# shiftregboard.net
KiCad netlist of a schematic drawn in EAGLE
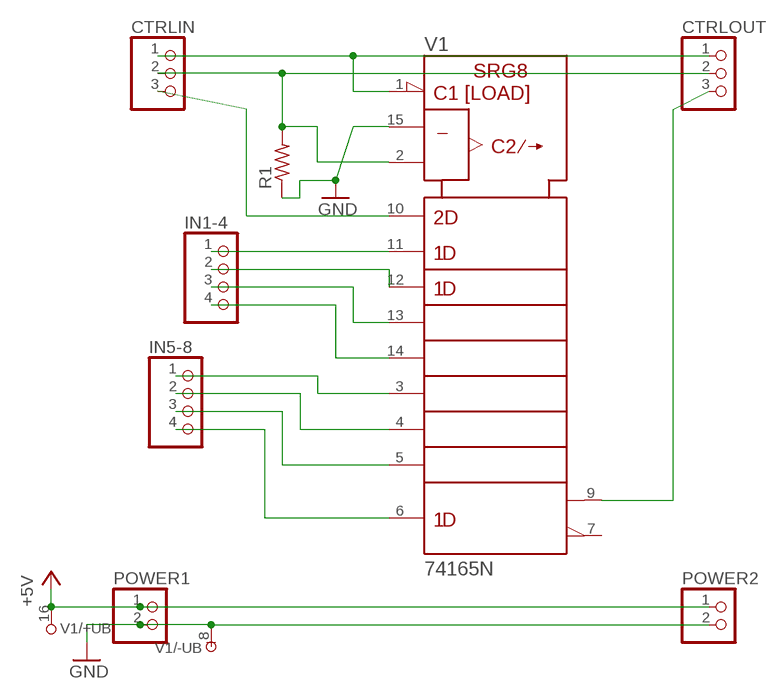
[diagram p0: schematic, sheet 1]

(export (version "E")
  (design (tool "Eeschema 10.0.6"))
  (components
    (comp (ref "CTRLIN")
      (value "PINHD-1X3")
      (footprint "eagle-import:1X03")
      (libsource (lib "eagle-import") (part "PINHD-1X3"))
    )
    (comp (ref "CTRLOUT")
      (value "PINHD-1X3")
      (footprint "eagle-import:1X03")
      (libsource (lib "eagle-import") (part "PINHD-1X3"))
    )
    (comp (ref "IN1-4")
      (value "PINHD-1X4")
      (footprint "eagle-import:1X04")
      (libsource (lib "eagle-import") (part "PINHD-1X4"))
    )
    (comp (ref "IN5-8")
      (value "PINHD-1X4")
      (footprint "eagle-import:1X04")
      (libsource (lib "eagle-import") (part "PINHD-1X4"))
    )
    (comp (ref "POWER1")
      (value "PINHD-1X2")
      (footprint "eagle-import:1X02")
      (libsource (lib "eagle-import") (part "PINHD-1X2"))
    )
    (comp (ref "POWER2")
      (value "PINHD-1X2")
      (footprint "eagle-import:1X02")
      (libsource (lib "eagle-import") (part "PINHD-1X2"))
    )
    (comp (ref "R1")
      (value "R-US_0207/15")
      (footprint "eagle-import:0207_15")
      (libsource (lib "eagle-import") (part "R-US_0207/15"))
    )
    (comp (ref "V1")
      (value "74165N")
      (footprint "eagle-import:DIL16")
      (libsource (lib "eagle-import") (part "74165N"))
    )
  )
  (nets
    (net (code "1") (name "+5V") (class "Default")
      (node (ref "POWER1") (pin "1") (pinfunction "1_1") (pintype "passive"))
      (node (ref "POWER2") (pin "1") (pinfunction "1_1") (pintype "passive"))
      (node (ref "V1") (pin "16") (pinfunction "+UB_16") (pintype "power_in"))
    )
    (net (code "2") (name "GND") (class "Default")
      (node (ref "POWER1") (pin "2") (pinfunction "2_2") (pintype "passive"))
      (node (ref "POWER2") (pin "2") (pinfunction "2_2") (pintype "passive"))
      (node (ref "R1") (pin "1") (pinfunction "1_1") (pintype "passive"))
      (node (ref "V1") (pin "15") (pinfunction "CLK_INH_15") (pintype "input"))
      (node (ref "V1") (pin "8") (pinfunction "-UB_8") (pintype "power_in"))
    )
    (net (code "3") (name "Net-(V1C-A)") (class "Default")
      (node (ref "IN1-4") (pin "1") (pinfunction "1_1") (pintype "passive"))
      (node (ref "V1") (pin "11") (pinfunction "A_11") (pintype "input"))
    )
    (net (code "4") (name "Net-(V1C-B)") (class "Default")
      (node (ref "IN1-4") (pin "2") (pinfunction "2_2") (pintype "passive"))
      (node (ref "V1") (pin "12") (pinfunction "B_12") (pintype "input"))
    )
    (net (code "5") (name "Net-(V1C-C)") (class "Default")
      (node (ref "IN1-4") (pin "3") (pinfunction "3_3") (pintype "passive"))
      (node (ref "V1") (pin "13") (pinfunction "C_13") (pintype "input"))
    )
    (net (code "6") (name "Net-(V1C-CLK)") (class "Default")
      (node (ref "CTRLIN") (pin "2") (pinfunction "2_2") (pintype "passive"))
      (node (ref "CTRLOUT") (pin "2") (pinfunction "2_2") (pintype "passive"))
      (node (ref "R1") (pin "2") (pinfunction "2_2") (pintype "passive"))
      (node (ref "V1") (pin "2") (pinfunction "CLK_2") (pintype "input"))
    )
    (net (code "7") (name "Net-(V1C-D)") (class "Default")
      (node (ref "IN1-4") (pin "4") (pinfunction "4_4") (pintype "passive"))
      (node (ref "V1") (pin "14") (pinfunction "D_14") (pintype "input"))
    )
    (net (code "8") (name "Net-(V1C-E)") (class "Default")
      (node (ref "IN5-8") (pin "1") (pinfunction "1_1") (pintype "passive"))
      (node (ref "V1") (pin "3") (pinfunction "E_3") (pintype "input"))
    )
    (net (code "9") (name "Net-(V1C-F)") (class "Default")
      (node (ref "IN5-8") (pin "2") (pinfunction "2_2") (pintype "passive"))
      (node (ref "V1") (pin "4") (pinfunction "F_4") (pintype "input"))
    )
    (net (code "10") (name "Net-(V1C-G)") (class "Default")
      (node (ref "IN5-8") (pin "3") (pinfunction "3_3") (pintype "passive"))
      (node (ref "V1") (pin "5") (pinfunction "G_5") (pintype "input"))
    )
    (net (code "11") (name "Net-(V1C-H)") (class "Default")
      (node (ref "IN5-8") (pin "4") (pinfunction "4_4") (pintype "passive"))
      (node (ref "V1") (pin "6") (pinfunction "H_6") (pintype "input"))
    )
    (net (code "12") (name "Net-(V1C-QH)") (class "Default")
      (node (ref "CTRLOUT") (pin "3") (pinfunction "3_3") (pintype "passive"))
      (node (ref "V1") (pin "9") (pinfunction "QH_9") (pintype "output"))
    )
    (net (code "13") (name "Net-(V1C-SER)") (class "Default")
      (node (ref "CTRLIN") (pin "3") (pinfunction "3_3") (pintype "passive"))
      (node (ref "V1") (pin "10") (pinfunction "SER_10") (pintype "input"))
    )
    (net (code "14") (name "Net-(V1C-SH{slash}~{LD})") (class "Default")
      (node (ref "CTRLIN") (pin "1") (pinfunction "1_1") (pintype "passive"))
      (node (ref "CTRLOUT") (pin "1") (pinfunction "1_1") (pintype "passive"))
      (node (ref "V1") (pin "1") (pinfunction "SH/~{LD}_1") (pintype "input"))
    )
    (net (code "15") (name "unconnected-(V1C-~{QH}-Pad7)") (class "Default")
      (node (ref "V1") (pin "7") (pinfunction "~{QH}_7") (pintype "output"))
    )
  )
)
